# Sheet2.net
KiCad netlist of a schematic drawn in Altium Designer
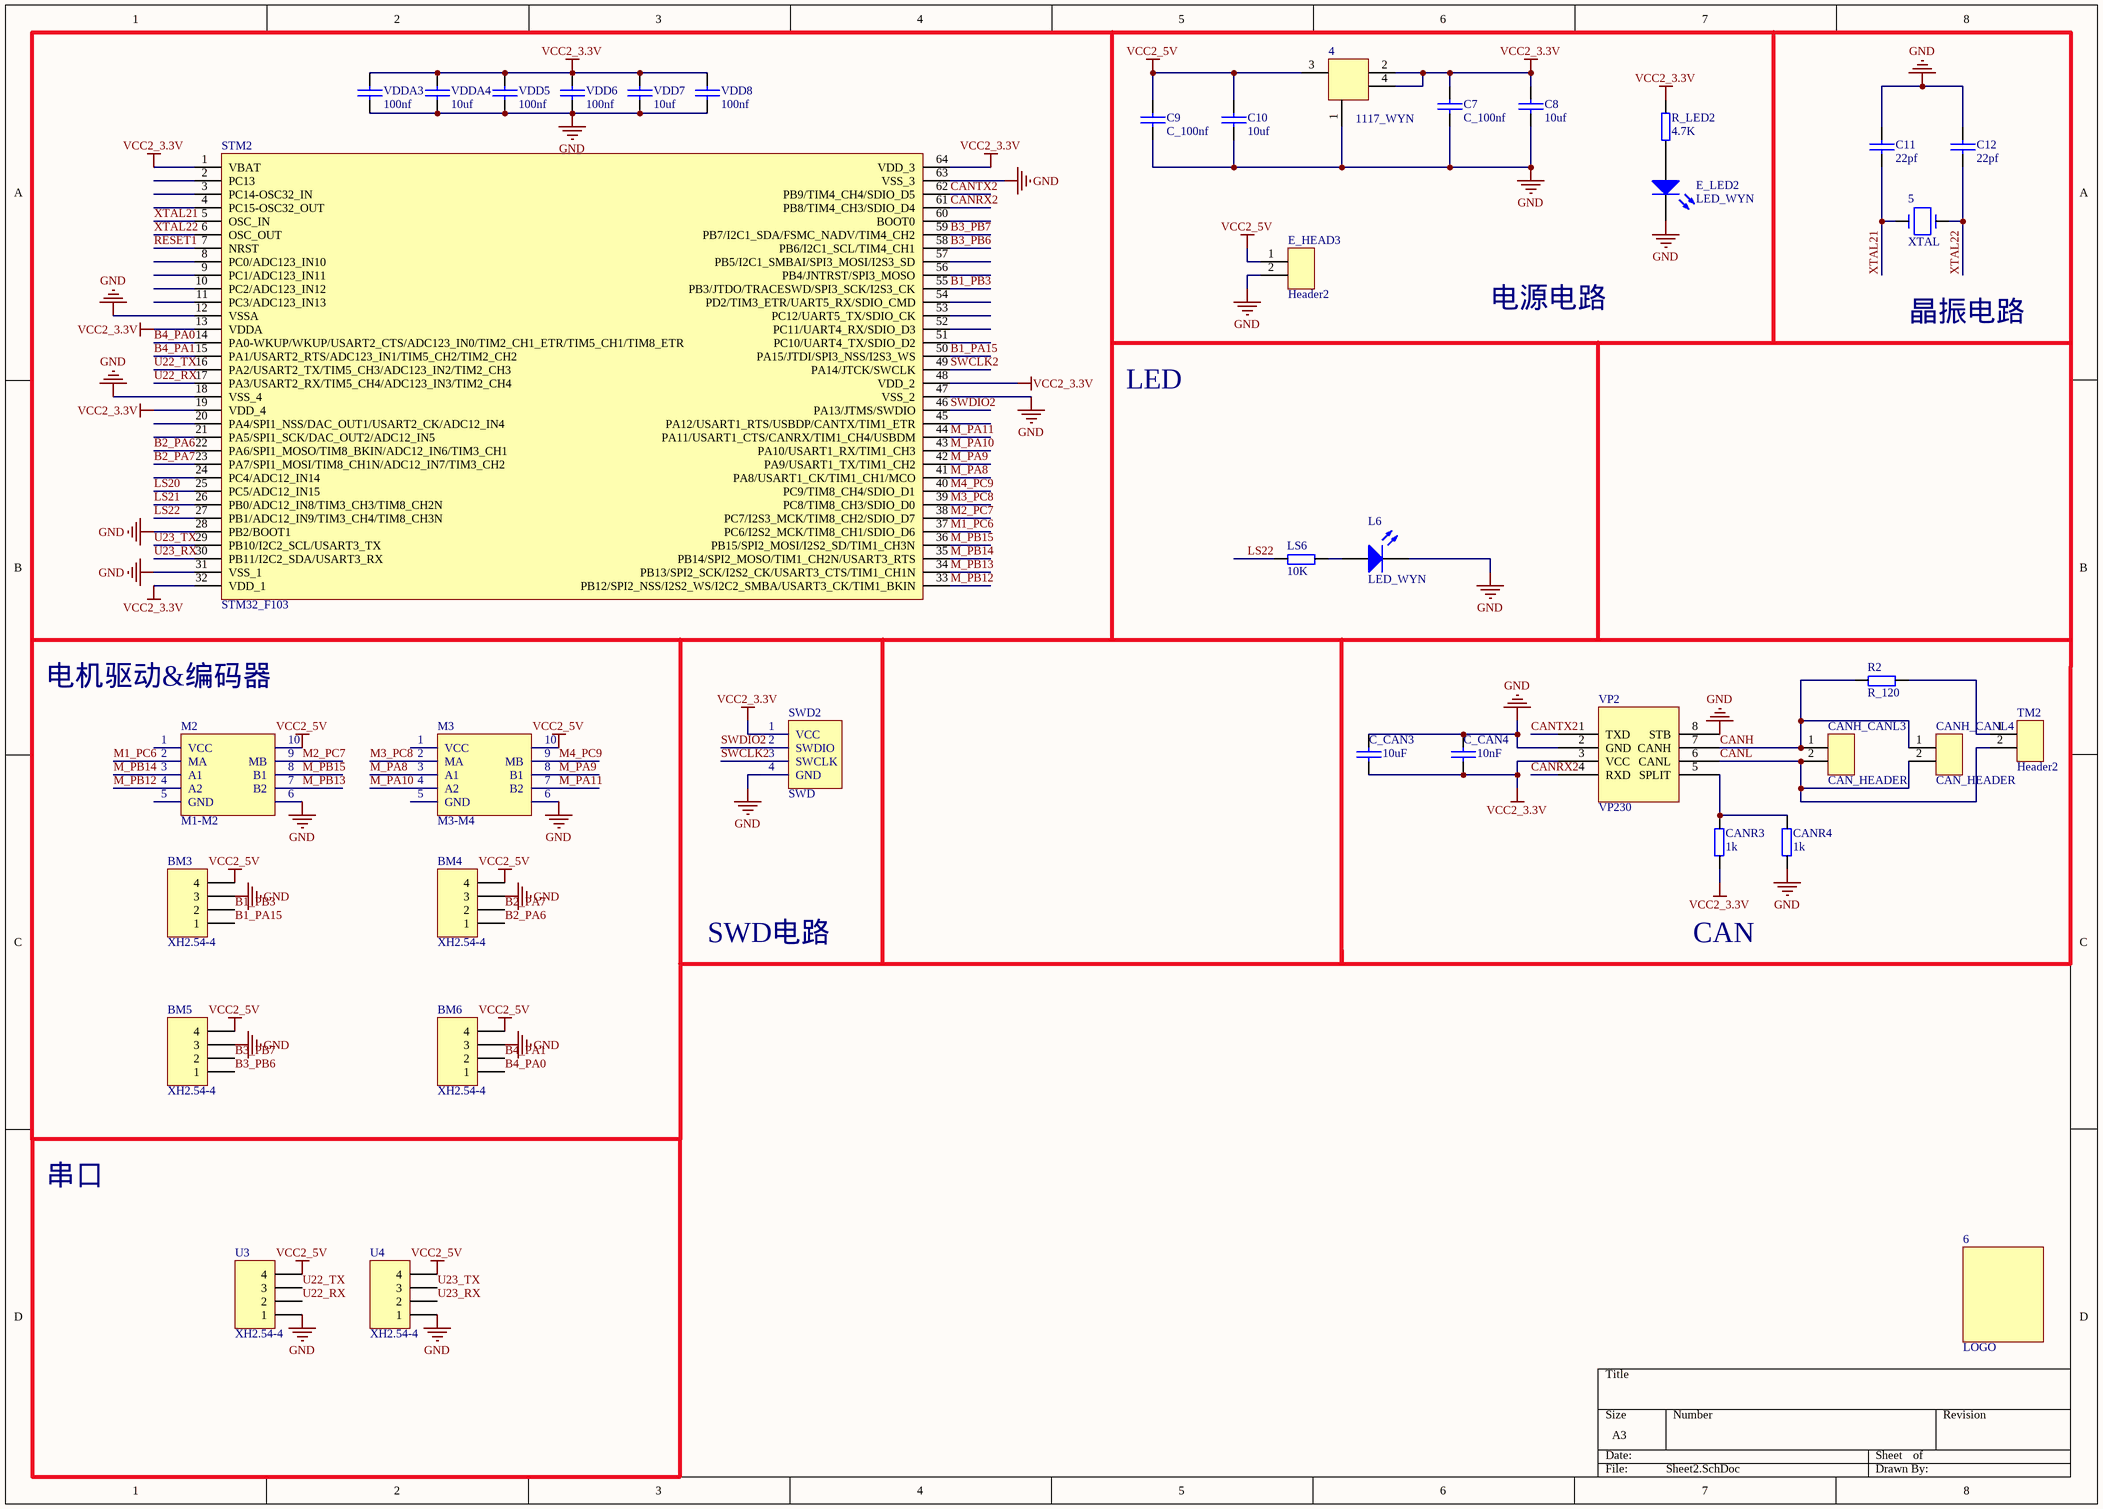
[diagram p0: Sheet2.SchDoc]

(export (version "E")
  (design (tool "Eeschema 10.0.6"))
  (components
    (comp (ref "4") (value "1117_WYN") (footprint "SOT223_M") (libsource (lib "STM32主处理板") (part "1117_WYN")))
    (comp (ref "5") (value "XTAL") (footprint "XTAL_D") (libsource (lib "STM32主处理板") (part "XTAL")))
    (comp (ref "6") (value "LOGO") (footprint "LOGO") (libsource (lib "STM32主处理板") (part "LOGO")))
    (comp (ref "BM3")
      (value "XH2.54-4")
      (footprint "XH2.54-4")
      (libsource (lib "my_library") (part "XH2.54-4"))
    )
    (comp (ref "BM4")
      (value "XH2.54-4")
      (footprint "XH2.54-4")
      (libsource (lib "my_library") (part "XH2.54-4"))
    )
    (comp (ref "BM5")
      (value "XH2.54-4")
      (footprint "XH2.54-4")
      (libsource (lib "my_library") (part "XH2.54-4"))
    )
    (comp (ref "BM6")
      (value "XH2.54-4")
      (footprint "XH2.54-4")
      (libsource (lib "my_library") (part "XH2.54-4"))
    )
    (comp (ref "C7") (value "C_100nf") (footprint "0603") (libsource (lib "STM32主处理板") (part "CAP_WYN")))
    (comp (ref "C8") (value "10uf") (footprint "0603") (libsource (lib "STM32主处理板") (part "CAP_WYN")))
    (comp (ref "C9") (value "C_100nf") (footprint "0603") (libsource (lib "STM32主处理板") (part "CAP_WYN")))
    (comp (ref "C10") (value "10uf") (footprint "0603") (libsource (lib "STM32主处理板") (part "CAP_WYN")))
    (comp (ref "C11") (value "22pf") (footprint "0603") (libsource (lib "STM32主处理板") (part "CAP_WYN")))
    (comp (ref "C12") (value "22pf") (footprint "0603") (libsource (lib "STM32主处理板") (part "CAP_WYN")))
    (comp (ref "CANH_CANL3")
      (value "CAN_HEADER")
      (footprint "CAN信号")
      (libsource (lib "STM32主处理板") (part "CAN_HEADER"))
    )
    (comp (ref "CANH_CANL4")
      (value "CAN_HEADER")
      (footprint "CAN信号")
      (libsource (lib "STM32主处理板") (part "CAN_HEADER"))
    )
    (comp (ref "CANR3") (value "1k") (footprint "0603_WYH") (libsource (lib "战舰STM32开发板底板封装库") (part "R")))
    (comp (ref "CANR4") (value "1k") (footprint "0603_WYH") (libsource (lib "战舰STM32开发板底板封装库") (part "R")))
    (comp (ref "C_CAN3") (value "10uF") (footprint "0603") (libsource (lib "STM32主处理板") (part "CAP_WYN")))
    (comp (ref "C_CAN4") (value "10nF") (footprint "0603") (libsource (lib "STM32主处理板") (part "CAP_WYN")))
    (comp (ref "E_HEAD3")
      (value "Header2")
      (footprint "POWER")
      (libsource (lib "STM32主处理板") (part "Header2"))
    )
    (comp (ref "E_LED2") (value "LED_WYN") (footprint "0603") (libsource (lib "STM32主处理板") (part "LED_WYN")))
    (comp (ref "L6") (value "LED_WYN") (footprint "0603") (libsource (lib "STM32主处理板") (part "LED_WYN")))
    (comp (ref "LS6") (value "10K") (footprint "0603_WYH") (libsource (lib "战舰STM32开发板底板封装库") (part "R")))
    (comp (ref "M2") (value "M1-M2") (footprint "JTAG_10to20") (libsource (lib "STM32主处理板") (part "电机接口")))
    (comp (ref "M3") (value "M3-M4") (footprint "JTAG_10to20") (libsource (lib "STM32主处理板") (part "电机接口")))
    (comp (ref "R2") (value "R_120") (footprint "0603_WYH") (libsource (lib "战舰STM32开发板底板封装库") (part "R")))
    (comp (ref "R_LED2") (value "4.7K") (footprint "0603") (libsource (lib "STM32主处理板") (part "RES_WYN")))
    (comp (ref "STM2")
      (value "STM32_F103")
      (footprint "STM32TSQFP50P1200X1200X160-64N")
      (libsource (lib "STM32主处理板") (part "STM32_F103"))
    )
    (comp (ref "SWD2") (value "SWD") (footprint "HDR1X5") (libsource (lib "my_library") (part "SWD")))
    (comp (ref "TM2") (value "Header2") (footprint "HDR1X2") (libsource (lib "STM32主处理板") (part "Header2")))
    (comp (ref "U3")
      (value "XH2.54-4")
      (footprint "XH2.54-4")
      (libsource (lib "my_library") (part "XH2.54-4"))
    )
    (comp (ref "U4")
      (value "XH2.54-4")
      (footprint "XH2.54-4")
      (libsource (lib "my_library") (part "XH2.54-4"))
    )
    (comp (ref "VDD5") (value "100nf") (footprint "0603") (libsource (lib "STM32主处理板") (part "CAP_WYN")))
    (comp (ref "VDD6") (value "100nf") (footprint "0603") (libsource (lib "STM32主处理板") (part "CAP_WYN")))
    (comp (ref "VDD7") (value "10uf") (footprint "0603") (libsource (lib "STM32主处理板") (part "CAP_WYN")))
    (comp (ref "VDD8") (value "100nf") (footprint "0603") (libsource (lib "STM32主处理板") (part "CAP_WYN")))
    (comp (ref "VDDA3") (value "100nf") (footprint "0603") (libsource (lib "STM32主处理板") (part "CAP_WYN")))
    (comp (ref "VDDA4") (value "10uf") (footprint "0603") (libsource (lib "STM32主处理板") (part "CAP_WYN")))
    (comp (ref "VP2") (value "VP230") (footprint "VP230") (libsource (lib "STM32主处理板") (part "VP230")))
  )
  (nets
    (net (code "1") (name "/B1_PA15") (class "Default")
      (node (ref "BM3") (pin "1") (pinfunction "1_1") (pintype "passive"))
      (node (ref "STM2") (pin "50") (pinfunction "PA15/JTDI/SPI3_NSS/I2S3_WS_50") (pintype "passive"))
    )
    (net (code "2") (name "/B1_PB3") (class "Default")
      (node (ref "BM3") (pin "2") (pinfunction "2_2") (pintype "passive"))
      (node (ref "STM2") (pin "55") (pinfunction "PB3/JTDO/TRACESWD/SPI3_SCK/I2S3_CK_55") (pintype "passive"))
    )
    (net (code "3") (name "/B2_PA6") (class "Default")
      (node (ref "BM4") (pin "1") (pinfunction "1_1") (pintype "passive"))
      (node (ref "STM2") (pin "22") (pinfunction "PA6/SPI1_MOSO/TIM8_BKIN/ADC12_IN6/TIM3_CH1_22") (pintype "passive"))
    )
    (net (code "4") (name "/B2_PA7") (class "Default")
      (node (ref "BM4") (pin "2") (pinfunction "2_2") (pintype "passive"))
      (node (ref "STM2") (pin "23") (pinfunction "PA7/SPI1_MOSI/TIM8_CH1N/ADC12_IN7/TIM3_CH2_23") (pintype "passive"))
    )
    (net (code "5") (name "/B3_PB6") (class "Default")
      (node (ref "BM5") (pin "1") (pinfunction "1_1") (pintype "passive"))
      (node (ref "STM2") (pin "58") (pinfunction "PB6/I2C1_SCL/TIM4_CH1_58") (pintype "passive"))
    )
    (net (code "6") (name "/B3_PB7") (class "Default")
      (node (ref "BM5") (pin "2") (pinfunction "2_2") (pintype "passive"))
      (node (ref "STM2") (pin "59") (pinfunction "PB7/I2C1_SDA/FSMC_NADV/TIM4_CH2_59") (pintype "passive"))
    )
    (net (code "7") (name "/B4_PA0") (class "Default")
      (node (ref "BM6") (pin "1") (pinfunction "1_1") (pintype "passive"))
      (node (ref "STM2") (pin "14") (pinfunction "PA0-WKUP/WKUP/USART2_CTS/ADC123_IN0/TIM2_CH1_ETR/TIM5_CH1/TIM8_ETR_14") (pintype "passive"))
    )
    (net (code "8") (name "/B4_PA1") (class "Default")
      (node (ref "BM6") (pin "2") (pinfunction "2_2") (pintype "passive"))
      (node (ref "STM2") (pin "15") (pinfunction "PA1/USART2_RTS/ADC123_IN1/TIM5_CH2/TIM2_CH2_15") (pintype "passive"))
    )
    (net (code "9") (name "/CANH") (class "Default")
      (node (ref "CANH_CANL3") (pin "1") (pintype "passive"))
      (node (ref "CANH_CANL4") (pin "1") (pintype "passive"))
      (node (ref "R2") (pin "1") (pintype "passive"))
      (node (ref "VP2") (pin "7") (pinfunction "CANH_7") (pintype "passive"))
    )
    (net (code "10") (name "/CANL") (class "Default")
      (node (ref "CANH_CANL3") (pin "2") (pintype "passive"))
      (node (ref "CANH_CANL4") (pin "2") (pintype "passive"))
      (node (ref "TM2") (pin "2") (pintype "passive"))
      (node (ref "VP2") (pin "6") (pinfunction "CANL_6") (pintype "passive"))
    )
    (net (code "11") (name "/CANRX2") (class "Default")
      (node (ref "STM2") (pin "61") (pinfunction "PB8/TIM4_CH3/SDIO_D4_61") (pintype "passive"))
      (node (ref "VP2") (pin "4") (pinfunction "RXD_4") (pintype "passive"))
    )
    (net (code "12") (name "/CANTX2") (class "Default")
      (node (ref "STM2") (pin "62") (pinfunction "PB9/TIM4_CH4/SDIO_D5_62") (pintype "passive"))
      (node (ref "VP2") (pin "1") (pinfunction "TXD_1") (pintype "passive"))
    )
    (net (code "13") (name "/LS20") (class "Default")
      (node (ref "STM2") (pin "25") (pinfunction "PC5/ADC12_IN15_25") (pintype "passive"))
    )
    (net (code "14") (name "/LS21") (class "Default")
      (node (ref "STM2") (pin "26") (pinfunction "PB0/ADC12_IN8/TIM3_CH3/TIM8_CH2N_26") (pintype "passive"))
    )
    (net (code "15") (name "/LS22") (class "Default")
      (node (ref "LS6") (pin "1") (pintype "passive"))
      (node (ref "STM2") (pin "27") (pinfunction "PB1/ADC12_IN9/TIM3_CH4/TIM8_CH3N_27") (pintype "passive"))
    )
    (net (code "16") (name "/M1_PC6") (class "Default")
      (node (ref "M2") (pin "2") (pinfunction "MA_2") (pintype "passive"))
      (node (ref "STM2") (pin "37") (pinfunction "PC6/I2S2_MCK/TIM8_CH1/SDIO_D6_37") (pintype "passive"))
    )
    (net (code "17") (name "/M2_PC7") (class "Default")
      (node (ref "M2") (pin "9") (pinfunction "MB_9") (pintype "passive"))
      (node (ref "STM2") (pin "38") (pinfunction "PC7/I2S3_MCK/TIM8_CH2/SDIO_D7_38") (pintype "passive"))
    )
    (net (code "18") (name "/M3_PC8") (class "Default")
      (node (ref "M3") (pin "2") (pinfunction "MA_2") (pintype "passive"))
      (node (ref "STM2") (pin "39") (pinfunction "PC8/TIM8_CH3/SDIO_D0_39") (pintype "passive"))
    )
    (net (code "19") (name "/M4_PC9") (class "Default")
      (node (ref "M3") (pin "9") (pinfunction "MB_9") (pintype "passive"))
      (node (ref "STM2") (pin "40") (pinfunction "PC9/TIM8_CH4/SDIO_D1_40") (pintype "passive"))
    )
    (net (code "20") (name "/M_PA8") (class "Default")
      (node (ref "M3") (pin "3") (pinfunction "A1_3") (pintype "passive"))
      (node (ref "STM2") (pin "41") (pinfunction "PA8/USART1_CK/TIM1_CH1/MCO_41") (pintype "passive"))
    )
    (net (code "21") (name "/M_PA9") (class "Default")
      (node (ref "M3") (pin "8") (pinfunction "B1_8") (pintype "passive"))
      (node (ref "STM2") (pin "42") (pinfunction "PA9/USART1_TX/TIM1_CH2_42") (pintype "passive"))
    )
    (net (code "22") (name "/M_PA10") (class "Default")
      (node (ref "M3") (pin "4") (pinfunction "A2_4") (pintype "passive"))
      (node (ref "STM2") (pin "43") (pinfunction "PA10/USART1_RX/TIM1_CH3_43") (pintype "passive"))
    )
    (net (code "23") (name "/M_PA11") (class "Default")
      (node (ref "M3") (pin "7") (pinfunction "B2_7") (pintype "passive"))
      (node (ref "STM2") (pin "44") (pinfunction "PA11/USART1_CTS/CANRX/TIM1_CH4/USBDM_44") (pintype "passive"))
    )
    (net (code "24") (name "/M_PB12") (class "Default")
      (node (ref "M2") (pin "4") (pinfunction "A2_4") (pintype "passive"))
      (node (ref "STM2") (pin "33") (pinfunction "PB12/SPI2_NSS/I2S2_WS/I2C2_SMBA/USART3_CK/TIM1_BKIN_33") (pintype "passive"))
    )
    (net (code "25") (name "/M_PB13") (class "Default")
      (node (ref "M2") (pin "7") (pinfunction "B2_7") (pintype "passive"))
      (node (ref "STM2") (pin "34") (pinfunction "PB13/SPI2_SCK/I2S2_CK/USART3_CTS/TIM1_CH1N_34") (pintype "passive"))
    )
    (net (code "26") (name "/M_PB14") (class "Default")
      (node (ref "M2") (pin "3") (pinfunction "A1_3") (pintype "passive"))
      (node (ref "STM2") (pin "35") (pinfunction "PB14/SPI2_MOSO/TIM1_CH2N/USART3_RTS_35") (pintype "passive"))
    )
    (net (code "27") (name "/M_PB15") (class "Default")
      (node (ref "M2") (pin "8") (pinfunction "B1_8") (pintype "passive"))
      (node (ref "STM2") (pin "36") (pinfunction "PB15/SPI2_MOSI/I2S2_SD/TIM1_CH3N_36") (pintype "passive"))
    )
    (net (code "28") (name "/RESET1") (class "Default")
      (node (ref "STM2") (pin "7") (pinfunction "NRST_7") (pintype "passive"))
    )
    (net (code "29") (name "/SWCLK2") (class "Default")
      (node (ref "STM2") (pin "49") (pinfunction "PA14/JTCK/SWCLK_49") (pintype "passive"))
      (node (ref "SWD2") (pin "3") (pinfunction "SWCLK_3") (pintype "passive"))
    )
    (net (code "30") (name "/SWDIO2") (class "Default")
      (node (ref "STM2") (pin "46") (pinfunction "PA13/JTMS/SWDIO_46") (pintype "passive"))
      (node (ref "SWD2") (pin "2") (pinfunction "SWDIO_2") (pintype "passive"))
    )
    (net (code "31") (name "/U22_RX") (class "Default")
      (node (ref "STM2") (pin "17") (pinfunction "PA3/USART2_RX/TIM5_CH4/ADC123_IN3/TIM2_CH4_17") (pintype "passive"))
      (node (ref "U3") (pin "2") (pinfunction "2_2") (pintype "passive"))
    )
    (net (code "32") (name "/U22_TX") (class "Default")
      (node (ref "STM2") (pin "16") (pinfunction "PA2/USART2_TX/TIM5_CH3/ADC123_IN2/TIM2_CH3_16") (pintype "passive"))
      (node (ref "U3") (pin "3") (pinfunction "3_3") (pintype "passive"))
    )
    (net (code "33") (name "/U23_RX") (class "Default")
      (node (ref "STM2") (pin "30") (pinfunction "PB11/I2C2_SDA/USART3_RX_30") (pintype "passive"))
      (node (ref "U4") (pin "2") (pinfunction "2_2") (pintype "passive"))
    )
    (net (code "34") (name "/U23_TX") (class "Default")
      (node (ref "STM2") (pin "29") (pinfunction "PB10/I2C2_SCL/USART3_TX_29") (pintype "passive"))
      (node (ref "U4") (pin "3") (pinfunction "3_3") (pintype "passive"))
    )
    (net (code "35") (name "/XTAL21") (class "Default")
      (node (ref "5") (pin "1") (pinfunction "1_1") (pintype "passive"))
      (node (ref "C11") (pin "2") (pintype "passive"))
      (node (ref "STM2") (pin "5") (pinfunction "OSC_IN_5") (pintype "passive"))
    )
    (net (code "36") (name "/XTAL22") (class "Default")
      (node (ref "5") (pin "2") (pinfunction "2_2") (pintype "passive"))
      (node (ref "C12") (pin "2") (pintype "passive"))
      (node (ref "STM2") (pin "6") (pinfunction "OSC_OUT_6") (pintype "passive"))
    )
    (net (code "37") (name "GND") (class "Default")
      (node (ref "4") (pin "1") (pintype "passive"))
      (node (ref "BM3") (pin "3") (pinfunction "3_3") (pintype "passive"))
      (node (ref "BM4") (pin "3") (pinfunction "3_3") (pintype "passive"))
      (node (ref "BM5") (pin "3") (pinfunction "3_3") (pintype "passive"))
      (node (ref "BM6") (pin "3") (pinfunction "3_3") (pintype "passive"))
      (node (ref "C10") (pin "2") (pintype "passive"))
      (node (ref "C11") (pin "1") (pintype "passive"))
      (node (ref "C12") (pin "1") (pintype "passive"))
      (node (ref "C7") (pin "2") (pintype "passive"))
      (node (ref "C8") (pin "2") (pintype "passive"))
      (node (ref "C9") (pin "2") (pintype "passive"))
      (node (ref "CANR4") (pin "2") (pintype "passive"))
      (node (ref "C_CAN3") (pin "1") (pintype "passive"))
      (node (ref "C_CAN4") (pin "1") (pintype "passive"))
      (node (ref "E_HEAD3") (pin "2") (pintype "passive"))
      (node (ref "E_LED2") (pin "2") (pinfunction "K_2") (pintype "passive"))
      (node (ref "L6") (pin "2") (pinfunction "K_2") (pintype "passive"))
      (node (ref "M2") (pin "6") (pintype "passive"))
      (node (ref "M3") (pin "6") (pintype "passive"))
      (node (ref "STM2") (pin "12") (pinfunction "VSSA_12") (pintype "passive"))
      (node (ref "STM2") (pin "18") (pinfunction "VSS_4_18") (pintype "passive"))
      (node (ref "STM2") (pin "28") (pinfunction "PB2/BOOT1_28") (pintype "passive"))
      (node (ref "STM2") (pin "31") (pinfunction "VSS_1_31") (pintype "passive"))
      (node (ref "STM2") (pin "47") (pinfunction "VSS_2_47") (pintype "passive"))
      (node (ref "STM2") (pin "63") (pinfunction "VSS_3_63") (pintype "passive"))
      (node (ref "SWD2") (pin "4") (pinfunction "GND_4") (pintype "passive"))
      (node (ref "U3") (pin "1") (pinfunction "1_1") (pintype "passive"))
      (node (ref "U4") (pin "1") (pinfunction "1_1") (pintype "passive"))
      (node (ref "VDD5") (pin "2") (pintype "passive"))
      (node (ref "VDD6") (pin "2") (pintype "passive"))
      (node (ref "VDD7") (pin "2") (pintype "passive"))
      (node (ref "VDD8") (pin "2") (pintype "passive"))
      (node (ref "VDDA3") (pin "2") (pintype "passive"))
      (node (ref "VDDA4") (pin "2") (pintype "passive"))
      (node (ref "VP2") (pin "2") (pinfunction "GND_2") (pintype "passive"))
      (node (ref "VP2") (pin "8") (pinfunction "STB_8") (pintype "passive"))
    )
    (net (code "38") (name "Net-(E_LED2-A)") (class "Default")
      (node (ref "E_LED2") (pin "1") (pinfunction "A_1") (pintype "passive"))
      (node (ref "R_LED2") (pin "1") (pinfunction "1_1") (pintype "passive"))
    )
    (net (code "39") (name "Net-(L6-A)") (class "Default")
      (node (ref "L6") (pin "1") (pinfunction "A_1") (pintype "passive"))
      (node (ref "LS6") (pin "2") (pintype "passive"))
    )
    (net (code "40") (name "Net-(R2-Pad2)") (class "Default")
      (node (ref "R2") (pin "2") (pintype "passive"))
      (node (ref "TM2") (pin "1") (pintype "passive"))
    )
    (net (code "41") (name "Net-(VP2-SPLIT)") (class "Default")
      (node (ref "CANR3") (pin "1") (pintype "passive"))
      (node (ref "CANR4") (pin "1") (pintype "passive"))
      (node (ref "VP2") (pin "5") (pinfunction "SPLIT_5") (pintype "passive"))
    )
    (net (code "42") (name "VCC2_3.3V") (class "Default")
      (node (ref "4") (pin "2") (pintype "passive"))
      (node (ref "4") (pin "4") (pintype "passive"))
      (node (ref "C7") (pin "1") (pintype "passive"))
      (node (ref "C8") (pin "1") (pintype "passive"))
      (node (ref "CANR3") (pin "2") (pintype "passive"))
      (node (ref "C_CAN3") (pin "2") (pintype "passive"))
      (node (ref "C_CAN4") (pin "2") (pintype "passive"))
      (node (ref "R_LED2") (pin "2") (pinfunction "2_2") (pintype "passive"))
      (node (ref "STM2") (pin "1") (pinfunction "VBAT_1") (pintype "passive"))
      (node (ref "STM2") (pin "13") (pinfunction "VDDA_13") (pintype "passive"))
      (node (ref "STM2") (pin "19") (pinfunction "VDD_4_19") (pintype "passive"))
      (node (ref "STM2") (pin "32") (pinfunction "VDD_1_32") (pintype "passive"))
      (node (ref "STM2") (pin "48") (pinfunction "VDD_2_48") (pintype "passive"))
      (node (ref "STM2") (pin "64") (pinfunction "VDD_3_64") (pintype "passive"))
      (node (ref "SWD2") (pin "1") (pinfunction "VCC_1") (pintype "passive"))
      (node (ref "VDD5") (pin "1") (pintype "passive"))
      (node (ref "VDD6") (pin "1") (pintype "passive"))
      (node (ref "VDD7") (pin "1") (pintype "passive"))
      (node (ref "VDD8") (pin "1") (pintype "passive"))
      (node (ref "VDDA3") (pin "1") (pintype "passive"))
      (node (ref "VDDA4") (pin "1") (pintype "passive"))
      (node (ref "VP2") (pin "3") (pinfunction "VCC_3") (pintype "passive"))
    )
    (net (code "43") (name "VCC2_5V") (class "Default")
      (node (ref "4") (pin "3") (pintype "passive"))
      (node (ref "BM3") (pin "4") (pinfunction "4_4") (pintype "passive"))
      (node (ref "BM4") (pin "4") (pinfunction "4_4") (pintype "passive"))
      (node (ref "BM5") (pin "4") (pinfunction "4_4") (pintype "passive"))
      (node (ref "BM6") (pin "4") (pinfunction "4_4") (pintype "passive"))
      (node (ref "C10") (pin "1") (pintype "passive"))
      (node (ref "C9") (pin "1") (pintype "passive"))
      (node (ref "E_HEAD3") (pin "1") (pintype "passive"))
      (node (ref "M2") (pin "10") (pintype "passive"))
      (node (ref "M3") (pin "10") (pintype "passive"))
      (node (ref "U3") (pin "4") (pinfunction "4_4") (pintype "passive"))
      (node (ref "U4") (pin "4") (pinfunction "4_4") (pintype "passive"))
    )
    (net (code "44") (name "unconnected-(M2-GND-Pad5)") (class "Default")
      (node (ref "M2") (pin "5") (pinfunction "GND_5") (pintype "passive"))
    )
    (net (code "45") (name "unconnected-(M2-VCC-Pad1)") (class "Default")
      (node (ref "M2") (pin "1") (pinfunction "VCC_1") (pintype "passive"))
    )
    (net (code "46") (name "unconnected-(M3-GND-Pad5)") (class "Default")
      (node (ref "M3") (pin "5") (pinfunction "GND_5") (pintype "passive"))
    )
    (net (code "47") (name "unconnected-(M3-VCC-Pad1)") (class "Default")
      (node (ref "M3") (pin "1") (pinfunction "VCC_1") (pintype "passive"))
    )
    (net (code "48") (name "unconnected-(STM2-BOOT0-Pad60)") (class "Default")
      (node (ref "STM2") (pin "60") (pinfunction "BOOT0_60") (pintype "passive"))
    )
    (net (code "49") (name "unconnected-(STM2-PA4{slash}SPI1_NSS{slash}DAC_OUT1{slash}USART2_CK{slash}ADC12_IN4-Pad20)") (class "Default")
      (node (ref "STM2") (pin "20") (pinfunction "PA4/SPI1_NSS/DAC_OUT1/USART2_CK/ADC12_IN4_20") (pintype "passive"))
    )
    (net (code "50") (name "unconnected-(STM2-PA5{slash}SPI1_SCK{slash}DAC_OUT2{slash}ADC12_IN5-Pad21)") (class "Default")
      (node (ref "STM2") (pin "21") (pinfunction "PA5/SPI1_SCK/DAC_OUT2/ADC12_IN5_21") (pintype "passive"))
    )
    (net (code "51") (name "unconnected-(STM2-PA12{slash}USART1_RTS{slash}USBDP{slash}CANTX{slash}TIM1_ETR-Pad45)") (class "Default")
      (node (ref "STM2") (pin "45") (pinfunction "PA12/USART1_RTS/USBDP/CANTX/TIM1_ETR_45") (pintype "passive"))
    )
    (net (code "52") (name "unconnected-(STM2-PB4{slash}JNTRST{slash}SPI3_MOSO-Pad56)") (class "Default")
      (node (ref "STM2") (pin "56") (pinfunction "PB4/JNTRST/SPI3_MOSO_56") (pintype "passive"))
    )
    (net (code "53") (name "unconnected-(STM2-PB5{slash}I2C1_SMBAI{slash}SPI3_MOSI{slash}I2S3_SD-Pad57)") (class "Default")
      (node (ref "STM2") (pin "57") (pinfunction "PB5/I2C1_SMBAI/SPI3_MOSI/I2S3_SD_57") (pintype "passive"))
    )
    (net (code "54") (name "unconnected-(STM2-PC0{slash}ADC123_IN10-Pad8)") (class "Default")
      (node (ref "STM2") (pin "8") (pinfunction "PC0/ADC123_IN10_8") (pintype "passive"))
    )
    (net (code "55") (name "unconnected-(STM2-PC1{slash}ADC123_IN11-Pad9)") (class "Default")
      (node (ref "STM2") (pin "9") (pinfunction "PC1/ADC123_IN11_9") (pintype "passive"))
    )
    (net (code "56") (name "unconnected-(STM2-PC2{slash}ADC123_IN12-Pad10)") (class "Default")
      (node (ref "STM2") (pin "10") (pinfunction "PC2/ADC123_IN12_10") (pintype "passive"))
    )
    (net (code "57") (name "unconnected-(STM2-PC3{slash}ADC123_IN13-Pad11)") (class "Default")
      (node (ref "STM2") (pin "11") (pinfunction "PC3/ADC123_IN13_11") (pintype "passive"))
    )
    (net (code "58") (name "unconnected-(STM2-PC4{slash}ADC12_IN14-Pad24)") (class "Default")
      (node (ref "STM2") (pin "24") (pinfunction "PC4/ADC12_IN14_24") (pintype "passive"))
    )
    (net (code "59") (name "unconnected-(STM2-PC10{slash}UART4_TX{slash}SDIO_D2-Pad51)") (class "Default")
      (node (ref "STM2") (pin "51") (pinfunction "PC10/UART4_TX/SDIO_D2_51") (pintype "passive"))
    )
    (net (code "60") (name "unconnected-(STM2-PC11{slash}UART4_RX{slash}SDIO_D3-Pad52)") (class "Default")
      (node (ref "STM2") (pin "52") (pinfunction "PC11/UART4_RX/SDIO_D3_52") (pintype "passive"))
    )
    (net (code "61") (name "unconnected-(STM2-PC12{slash}UART5_TX{slash}SDIO_CK-Pad53)") (class "Default")
      (node (ref "STM2") (pin "53") (pinfunction "PC12/UART5_TX/SDIO_CK_53") (pintype "passive"))
    )
    (net (code "62") (name "unconnected-(STM2-PC13-Pad2)") (class "Default")
      (node (ref "STM2") (pin "2") (pinfunction "PC13_2") (pintype "passive"))
    )
    (net (code "63") (name "unconnected-(STM2-PC14-OSC32_IN-Pad3)") (class "Default")
      (node (ref "STM2") (pin "3") (pinfunction "PC14-OSC32_IN_3") (pintype "passive"))
    )
    (net (code "64") (name "unconnected-(STM2-PC15-OSC32_OUT-Pad4)") (class "Default")
      (node (ref "STM2") (pin "4") (pinfunction "PC15-OSC32_OUT_4") (pintype "passive"))
    )
    (net (code "65") (name "unconnected-(STM2-PD2{slash}TIM3_ETR{slash}UART5_RX{slash}SDIO_CMD-Pad54)") (class "Default")
      (node (ref "STM2") (pin "54") (pinfunction "PD2/TIM3_ETR/UART5_RX/SDIO_CMD_54") (pintype "passive"))
    )
  )
)
